# pwr.net
KiCad netlist of a schematic drawn in Altium Designer
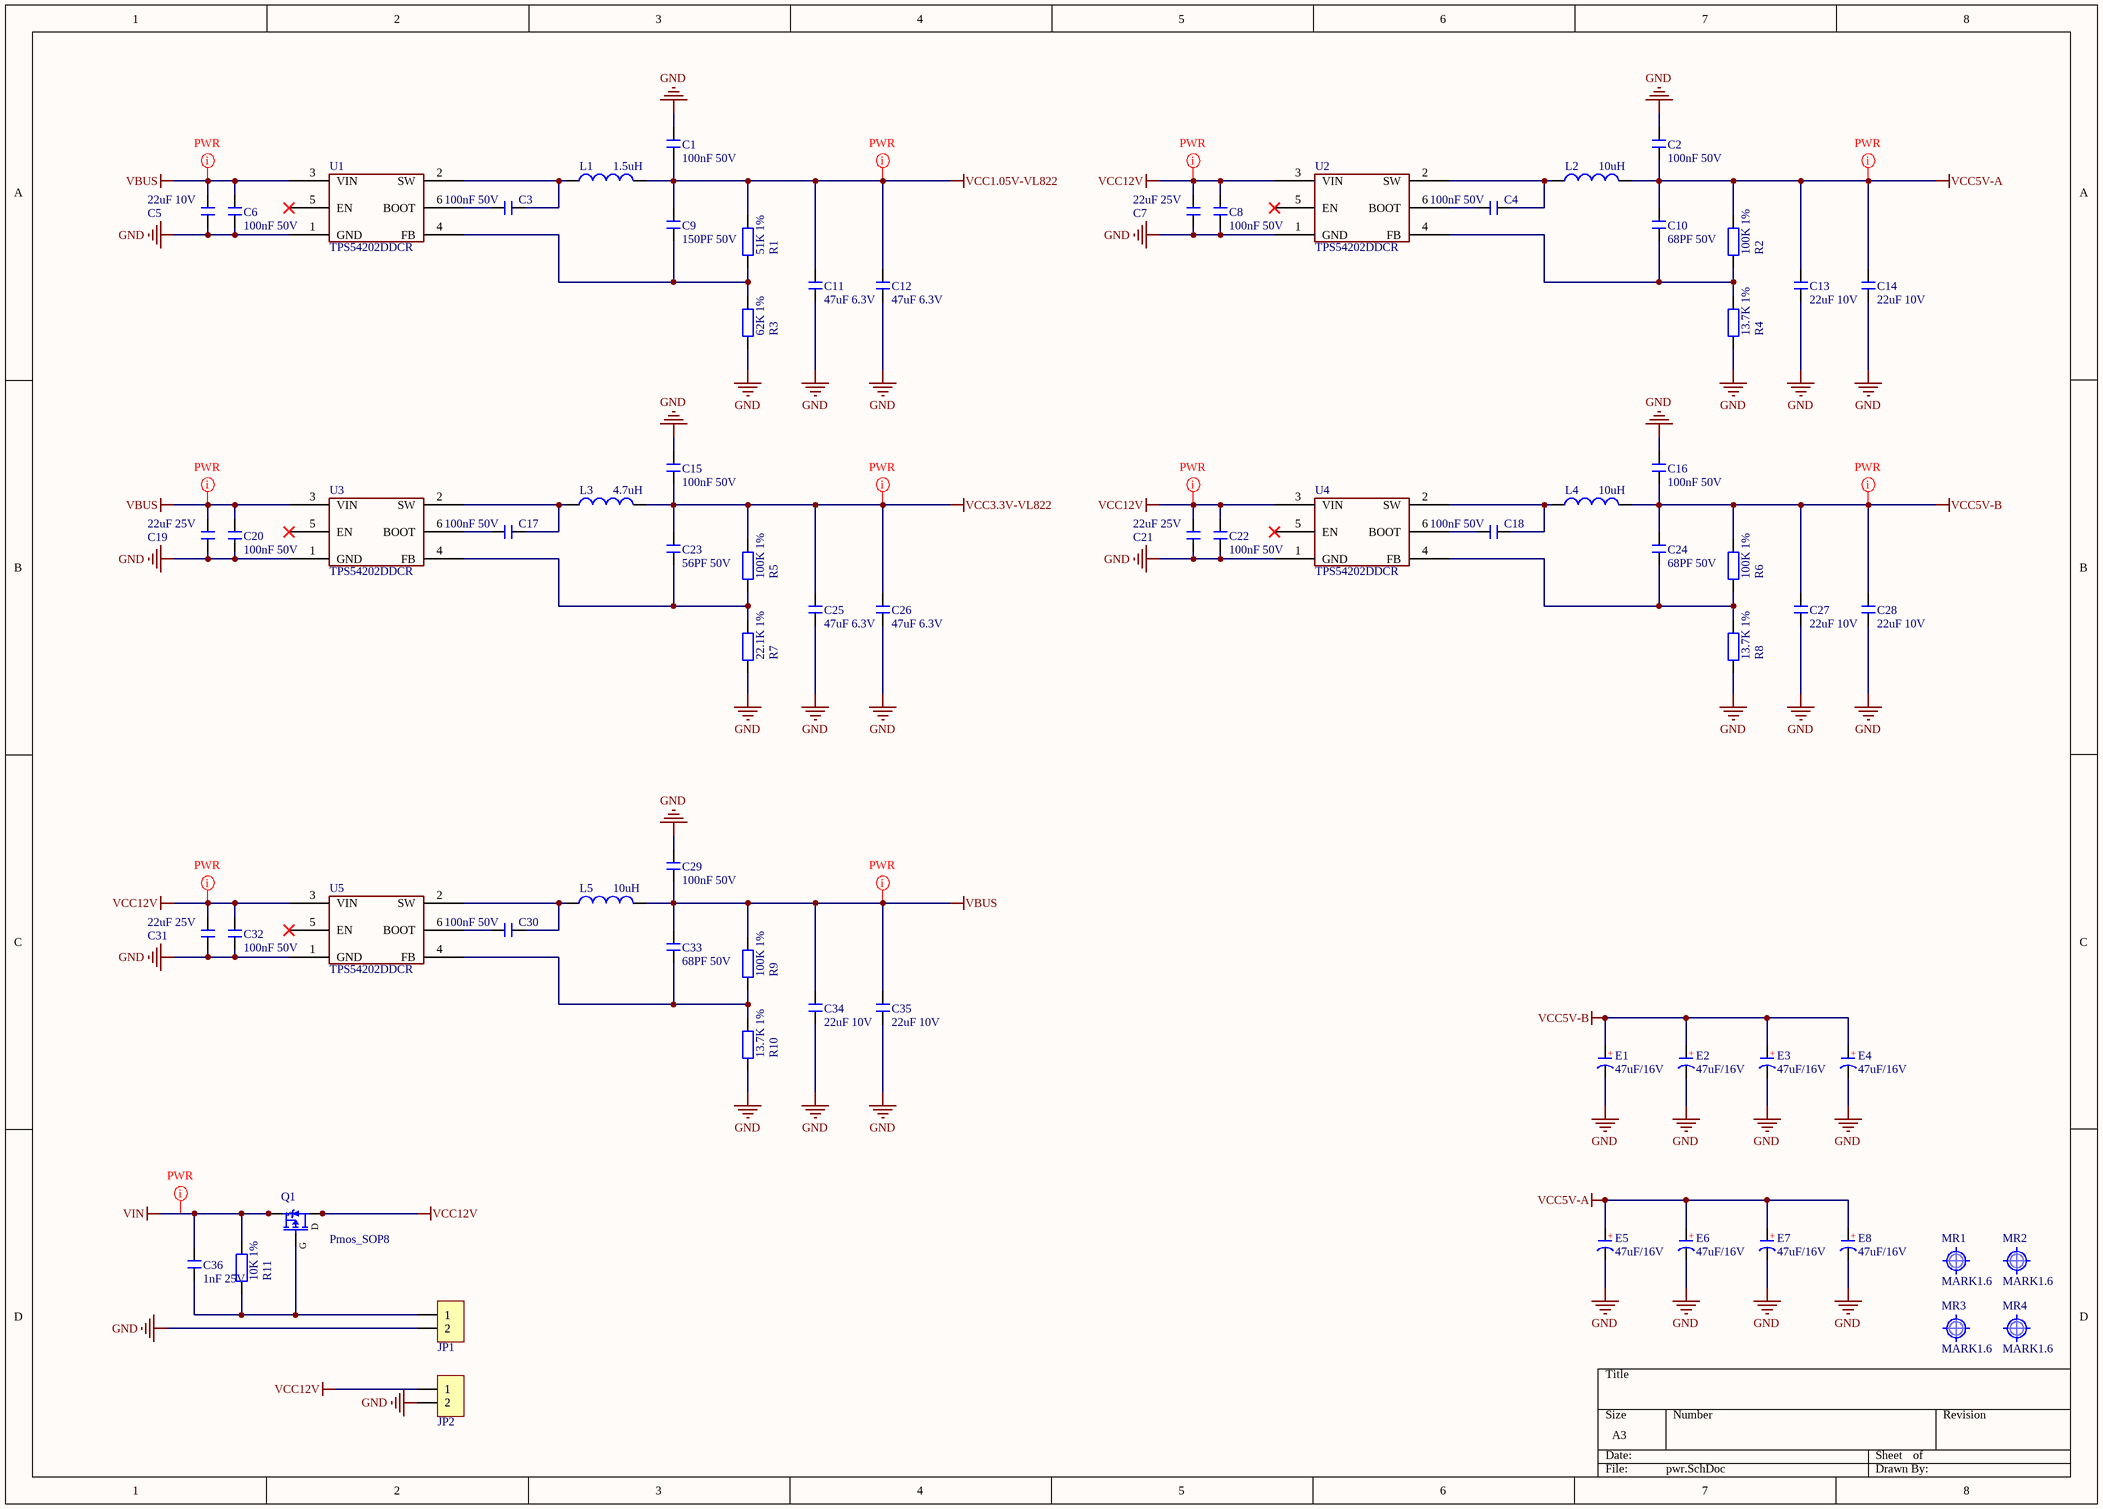
[diagram p0: pwr.SchDoc]

(export (version "E")
  (design (tool "Eeschema 10.0.6"))
  (components
    (comp (ref "C1")
      (value "100nF 50V")
      (footprint "C0402_L")
      (description "无极性贴片电容")
      (fields (field (name "版权归属") "源创客"))
      (libsource (lib "Capacitor") (part "C"))
    )
    (comp (ref "C2")
      (value "100nF 50V")
      (footprint "C0402_L")
      (description "无极性贴片电容")
      (fields (field (name "版权归属") "源创客"))
      (libsource (lib "Capacitor") (part "C"))
    )
    (comp (ref "C3")
      (value "100nF 50V")
      (footprint "C0402_L")
      (description "无极性贴片电容")
      (fields (field (name "版权归属") "源创客"))
      (libsource (lib "Capacitor") (part "C"))
    )
    (comp (ref "C4")
      (value "100nF 50V")
      (footprint "C0402_L")
      (description "无极性贴片电容")
      (fields (field (name "版权归属") "源创客"))
      (libsource (lib "Capacitor") (part "C"))
    )
    (comp (ref "C5")
      (value "22uF 10V")
      (footprint "C0805_L")
      (description "无极性贴片电容")
      (fields (field (name "版权归属") "源创客"))
      (libsource (lib "Capacitor") (part "C"))
    )
    (comp (ref "C6")
      (value "100nF 50V")
      (footprint "C0402_L")
      (description "无极性贴片电容")
      (fields (field (name "版权归属") "源创客"))
      (libsource (lib "Capacitor") (part "C"))
    )
    (comp (ref "C7")
      (value "22uF 25V")
      (footprint "C0805_L")
      (description "无极性贴片电容")
      (fields (field (name "版权归属") "源创客"))
      (libsource (lib "Capacitor") (part "C"))
    )
    (comp (ref "C8")
      (value "100nF 50V")
      (footprint "C0402_L")
      (description "无极性贴片电容")
      (fields (field (name "版权归属") "源创客"))
      (libsource (lib "Capacitor") (part "C"))
    )
    (comp (ref "C9")
      (value "150PF 50V")
      (footprint "C0402_L")
      (description "无极性贴片电容")
      (fields (field (name "版权归属") "源创客"))
      (libsource (lib "Capacitor") (part "C"))
    )
    (comp (ref "C10")
      (value "68PF 50V")
      (footprint "C0402_L")
      (description "无极性贴片电容")
      (fields (field (name "版权归属") "源创客"))
      (libsource (lib "Capacitor") (part "C"))
    )
    (comp (ref "C11")
      (value "47uF 6.3V")
      (footprint "C0805_L")
      (description "无极性贴片电容")
      (fields (field (name "版权归属") "源创客"))
      (libsource (lib "Capacitor") (part "C"))
    )
    (comp (ref "C12")
      (value "47uF 6.3V")
      (footprint "C0805_L")
      (description "无极性贴片电容")
      (fields (field (name "版权归属") "源创客"))
      (libsource (lib "Capacitor") (part "C"))
    )
    (comp (ref "C13")
      (value "22uF 10V")
      (footprint "C0805_L")
      (description "无极性贴片电容")
      (fields (field (name "版权归属") "源创客"))
      (libsource (lib "Capacitor") (part "C"))
    )
    (comp (ref "C14")
      (value "22uF 10V")
      (footprint "C0805_L")
      (description "无极性贴片电容")
      (fields (field (name "版权归属") "源创客"))
      (libsource (lib "Capacitor") (part "C"))
    )
    (comp (ref "C15")
      (value "100nF 50V")
      (footprint "C0402_L")
      (description "无极性贴片电容")
      (fields (field (name "版权归属") "源创客"))
      (libsource (lib "Capacitor") (part "C"))
    )
    (comp (ref "C16")
      (value "100nF 50V")
      (footprint "C0402_L")
      (description "无极性贴片电容")
      (fields (field (name "版权归属") "源创客"))
      (libsource (lib "Capacitor") (part "C"))
    )
    (comp (ref "C17")
      (value "100nF 50V")
      (footprint "C0402_L")
      (description "无极性贴片电容")
      (fields (field (name "版权归属") "源创客"))
      (libsource (lib "Capacitor") (part "C"))
    )
    (comp (ref "C18")
      (value "100nF 50V")
      (footprint "C0402_L")
      (description "无极性贴片电容")
      (fields (field (name "版权归属") "源创客"))
      (libsource (lib "Capacitor") (part "C"))
    )
    (comp (ref "C19")
      (value "22uF 25V")
      (footprint "C0805_L")
      (description "无极性贴片电容")
      (fields (field (name "版权归属") "源创客"))
      (libsource (lib "Capacitor") (part "C"))
    )
    (comp (ref "C20")
      (value "100nF 50V")
      (footprint "C0402_L")
      (description "无极性贴片电容")
      (fields (field (name "版权归属") "源创客"))
      (libsource (lib "Capacitor") (part "C"))
    )
    (comp (ref "C21")
      (value "22uF 25V")
      (footprint "C0805_L")
      (description "无极性贴片电容")
      (fields (field (name "版权归属") "源创客"))
      (libsource (lib "Capacitor") (part "C"))
    )
    (comp (ref "C22")
      (value "100nF 50V")
      (footprint "C0402_L")
      (description "无极性贴片电容")
      (fields (field (name "版权归属") "源创客"))
      (libsource (lib "Capacitor") (part "C"))
    )
    (comp (ref "C23")
      (value "56PF 50V")
      (footprint "C0402_L")
      (description "无极性贴片电容")
      (fields (field (name "版权归属") "源创客"))
      (libsource (lib "Capacitor") (part "C"))
    )
    (comp (ref "C24")
      (value "68PF 50V")
      (footprint "C0402_L")
      (description "无极性贴片电容")
      (fields (field (name "版权归属") "源创客"))
      (libsource (lib "Capacitor") (part "C"))
    )
    (comp (ref "C25")
      (value "47uF 6.3V")
      (footprint "C0805_L")
      (description "无极性贴片电容")
      (fields (field (name "版权归属") "源创客"))
      (libsource (lib "Capacitor") (part "C"))
    )
    (comp (ref "C26")
      (value "47uF 6.3V")
      (footprint "C0805_L")
      (description "无极性贴片电容")
      (fields (field (name "版权归属") "源创客"))
      (libsource (lib "Capacitor") (part "C"))
    )
    (comp (ref "C27")
      (value "22uF 10V")
      (footprint "C0805_L")
      (description "无极性贴片电容")
      (fields (field (name "版权归属") "源创客"))
      (libsource (lib "Capacitor") (part "C"))
    )
    (comp (ref "C28")
      (value "22uF 10V")
      (footprint "C0805_L")
      (description "无极性贴片电容")
      (fields (field (name "版权归属") "源创客"))
      (libsource (lib "Capacitor") (part "C"))
    )
    (comp (ref "C29")
      (value "100nF 50V")
      (footprint "C0402_L")
      (description "无极性贴片电容")
      (fields (field (name "版权归属") "源创客"))
      (libsource (lib "Capacitor") (part "C"))
    )
    (comp (ref "C30")
      (value "100nF 50V")
      (footprint "C0402_L")
      (description "无极性贴片电容")
      (fields (field (name "版权归属") "源创客"))
      (libsource (lib "Capacitor") (part "C"))
    )
    (comp (ref "C31")
      (value "22uF 25V")
      (footprint "C0805_L")
      (description "无极性贴片电容")
      (fields (field (name "版权归属") "源创客"))
      (libsource (lib "Capacitor") (part "C"))
    )
    (comp (ref "C32")
      (value "100nF 50V")
      (footprint "C0402_L")
      (description "无极性贴片电容")
      (fields (field (name "版权归属") "源创客"))
      (libsource (lib "Capacitor") (part "C"))
    )
    (comp (ref "C33")
      (value "68PF 50V")
      (footprint "C0402_L")
      (description "无极性贴片电容")
      (fields (field (name "版权归属") "源创客"))
      (libsource (lib "Capacitor") (part "C"))
    )
    (comp (ref "C34")
      (value "22uF 10V")
      (footprint "C0805_L")
      (description "无极性贴片电容")
      (fields (field (name "版权归属") "源创客"))
      (libsource (lib "Capacitor") (part "C"))
    )
    (comp (ref "C35")
      (value "22uF 10V")
      (footprint "C0805_L")
      (description "无极性贴片电容")
      (fields (field (name "版权归属") "源创客"))
      (libsource (lib "Capacitor") (part "C"))
    )
    (comp (ref "C36")
      (value "1nF 25V")
      (footprint "C0402_L")
      (description "无极性贴片电容")
      (fields (field (name "版权归属") "源创客"))
      (libsource (lib "Capacitor") (part "C"))
    )
    (comp (ref "E1")
      (value "47uF/16V")
      (footprint "CS 6*4 - R")
      (description "贴片电解电容")
      (fields (field (name "版权归属") "源创客"))
      (libsource (lib "Capacitor") (part "C-CD"))
    )
    (comp (ref "E2")
      (value "47uF/16V")
      (footprint "CS 6*4 - R")
      (description "贴片电解电容")
      (fields (field (name "版权归属") "源创客"))
      (libsource (lib "Capacitor") (part "C-CD"))
    )
    (comp (ref "E3")
      (value "47uF/16V")
      (footprint "CS 6*4 - R")
      (description "贴片电解电容")
      (fields (field (name "版权归属") "源创客"))
      (libsource (lib "Capacitor") (part "C-CD"))
    )
    (comp (ref "E4")
      (value "47uF/16V")
      (footprint "CS 6*4 - R")
      (description "贴片电解电容")
      (fields (field (name "版权归属") "源创客"))
      (libsource (lib "Capacitor") (part "C-CD"))
    )
    (comp (ref "E5")
      (value "47uF/16V")
      (footprint "CS 6*4 - R")
      (description "贴片电解电容")
      (fields (field (name "版权归属") "源创客"))
      (libsource (lib "Capacitor") (part "C-CD"))
    )
    (comp (ref "E6")
      (value "47uF/16V")
      (footprint "CS 6*4 - R")
      (description "贴片电解电容")
      (fields (field (name "版权归属") "源创客"))
      (libsource (lib "Capacitor") (part "C-CD"))
    )
    (comp (ref "E7")
      (value "47uF/16V")
      (footprint "CS 6*4 - R")
      (description "贴片电解电容")
      (fields (field (name "版权归属") "源创客"))
      (libsource (lib "Capacitor") (part "C-CD"))
    )
    (comp (ref "E8")
      (value "47uF/16V")
      (footprint "CS 6*4 - R")
      (description "贴片电解电容")
      (fields (field (name "版权归属") "源创客"))
      (libsource (lib "Capacitor") (part "C-CD"))
    )
    (comp (ref "JP1")
      (value "HDR-1X2")
      (footprint "ZH1.5-WS-2P")
      (description "2P接插件")
      (fields (field (name "版权归属") "源创客"))
      (libsource (lib "Connector-PinHeader") (part "Header 2"))
    )
    (comp (ref "JP2")
      (value "HDR-1X2")
      (footprint "XH2.54-WS-2P")
      (description "2P接插件")
      (fields (field (name "版权归属") "源创客"))
      (libsource (lib "Connector-PinHeader") (part "Header 2"))
    )
    (comp (ref "L1")
      (value "1.5uH")
      (footprint "SMMS0420")
      (description "小功率贴片电感")
      (fields (field (name "版权归属") "源创客"))
      (libsource (lib "Inductor") (part "L"))
    )
    (comp (ref "L2")
      (value "10uH")
      (footprint "SMMS0420")
      (description "小功率贴片电感")
      (fields (field (name "版权归属") "源创客"))
      (libsource (lib "Inductor") (part "L"))
    )
    (comp (ref "L3")
      (value "4.7uH")
      (footprint "SMMS0420")
      (description "小功率贴片电感")
      (fields (field (name "版权归属") "源创客"))
      (libsource (lib "Inductor") (part "L"))
    )
    (comp (ref "L4")
      (value "10uH")
      (footprint "SMMS0420")
      (description "小功率贴片电感")
      (fields (field (name "版权归属") "源创客"))
      (libsource (lib "Inductor") (part "L"))
    )
    (comp (ref "L5")
      (value "10uH")
      (footprint "SMMS0420")
      (description "小功率贴片电感")
      (fields (field (name "版权归属") "源创客"))
      (libsource (lib "Inductor") (part "L"))
    )
    (comp (ref "MR1")
      (value "MARK1.6")
      (footprint "Mark 1")
      (description "光学定位点")
      (fields (field (name "版权归属") "源创客"))
      (libsource (lib "Hole") (part "MARK"))
    )
    (comp (ref "MR2")
      (value "MARK1.6")
      (footprint "Mark 1")
      (description "光学定位点")
      (fields (field (name "版权归属") "源创客"))
      (libsource (lib "Hole") (part "MARK"))
    )
    (comp (ref "MR3")
      (value "MARK1.6")
      (footprint "Mark 1")
      (description "光学定位点")
      (fields (field (name "版权归属") "源创客"))
      (libsource (lib "Hole") (part "MARK"))
    )
    (comp (ref "MR4")
      (value "MARK1.6")
      (footprint "Mark 1")
      (description "光学定位点")
      (fields (field (name "版权归属") "源创客"))
      (libsource (lib "Hole") (part "MARK"))
    )
    (comp (ref "Q1")
      (value "Pmos_SOP8")
      (footprint "SOP8_L")
      (fields (field (name "版权归属") "源创客"))
      (libsource (lib "MOSFET BJT IGBT") (part "Pmos_SOP8"))
    )
    (comp (ref "R1")
      (value "51K 1%")
      (footprint "R0402_L")
      (description "贴片电阻")
      (fields (field (name "版权归属") "源创客"))
      (libsource (lib "Resistor") (part "R"))
    )
    (comp (ref "R2")
      (value "100K 1%")
      (footprint "R0402_L")
      (description "贴片电阻")
      (fields (field (name "版权归属") "源创客"))
      (libsource (lib "Resistor") (part "R"))
    )
    (comp (ref "R3")
      (value "62K 1%")
      (footprint "R0402_L")
      (description "贴片电阻")
      (fields (field (name "版权归属") "源创客"))
      (libsource (lib "Resistor") (part "R"))
    )
    (comp (ref "R4")
      (value "13.7K 1%")
      (footprint "R0402_L")
      (description "贴片电阻")
      (fields (field (name "版权归属") "源创客"))
      (libsource (lib "Resistor") (part "R"))
    )
    (comp (ref "R5")
      (value "100K 1%")
      (footprint "R0402_L")
      (description "贴片电阻")
      (fields (field (name "版权归属") "源创客"))
      (libsource (lib "Resistor") (part "R"))
    )
    (comp (ref "R6")
      (value "100K 1%")
      (footprint "R0402_L")
      (description "贴片电阻")
      (fields (field (name "版权归属") "源创客"))
      (libsource (lib "Resistor") (part "R"))
    )
    (comp (ref "R7")
      (value "22.1K 1%")
      (footprint "R0402_L")
      (description "贴片电阻")
      (fields (field (name "版权归属") "源创客"))
      (libsource (lib "Resistor") (part "R"))
    )
    (comp (ref "R8")
      (value "13.7K 1%")
      (footprint "R0402_L")
      (description "贴片电阻")
      (fields (field (name "版权归属") "源创客"))
      (libsource (lib "Resistor") (part "R"))
    )
    (comp (ref "R9")
      (value "100K 1%")
      (footprint "R0402_L")
      (description "贴片电阻")
      (fields (field (name "版权归属") "源创客"))
      (libsource (lib "Resistor") (part "R"))
    )
    (comp (ref "R10")
      (value "13.7K 1%")
      (footprint "R0402_L")
      (description "贴片电阻")
      (fields (field (name "版权归属") "源创客"))
      (libsource (lib "Resistor") (part "R"))
    )
    (comp (ref "R11")
      (value "10K 1%")
      (footprint "R0402_L")
      (description "贴片电阻")
      (fields (field (name "版权归属") "源创客"))
      (libsource (lib "Resistor") (part "R"))
    )
    (comp (ref "U1")
      (value "TPS54202DDCR")
      (footprint "SOT23-6L")
      (description "DCDC Convert")
      (libsource (lib "DCDC Convert") (part "TPS54202DDCR"))
    )
    (comp (ref "U2")
      (value "TPS54202DDCR")
      (footprint "SOT23-6L")
      (description "DCDC Convert")
      (libsource (lib "DCDC Convert") (part "TPS54202DDCR"))
    )
    (comp (ref "U3")
      (value "TPS54202DDCR")
      (footprint "SOT23-6L")
      (description "DCDC Convert")
      (libsource (lib "DCDC Convert") (part "TPS54202DDCR"))
    )
    (comp (ref "U4")
      (value "TPS54202DDCR")
      (footprint "SOT23-6L")
      (description "DCDC Convert")
      (libsource (lib "DCDC Convert") (part "TPS54202DDCR"))
    )
    (comp (ref "U5")
      (value "TPS54202DDCR")
      (footprint "SOT23-6L")
      (description "DCDC Convert")
      (libsource (lib "DCDC Convert") (part "TPS54202DDCR"))
    )
  )
  (nets
    (net (code "1") (name "GND") (class "Default")
      (node (ref "C1") (pin "2") (pinfunction "2_2") (pintype "passive"))
      (node (ref "C11") (pin "2") (pinfunction "2_2") (pintype "passive"))
      (node (ref "C12") (pin "2") (pinfunction "2_2") (pintype "passive"))
      (node (ref "C13") (pin "2") (pinfunction "2_2") (pintype "passive"))
      (node (ref "C14") (pin "2") (pinfunction "2_2") (pintype "passive"))
      (node (ref "C15") (pin "2") (pinfunction "2_2") (pintype "passive"))
      (node (ref "C16") (pin "2") (pinfunction "2_2") (pintype "passive"))
      (node (ref "C19") (pin "1") (pinfunction "1_1") (pintype "passive"))
      (node (ref "C2") (pin "2") (pinfunction "2_2") (pintype "passive"))
      (node (ref "C20") (pin "1") (pinfunction "1_1") (pintype "passive"))
      (node (ref "C21") (pin "1") (pinfunction "1_1") (pintype "passive"))
      (node (ref "C22") (pin "1") (pinfunction "1_1") (pintype "passive"))
      (node (ref "C25") (pin "2") (pinfunction "2_2") (pintype "passive"))
      (node (ref "C26") (pin "2") (pinfunction "2_2") (pintype "passive"))
      (node (ref "C27") (pin "2") (pinfunction "2_2") (pintype "passive"))
      (node (ref "C28") (pin "2") (pinfunction "2_2") (pintype "passive"))
      (node (ref "C29") (pin "2") (pinfunction "2_2") (pintype "passive"))
      (node (ref "C31") (pin "1") (pinfunction "1_1") (pintype "passive"))
      (node (ref "C32") (pin "1") (pinfunction "1_1") (pintype "passive"))
      (node (ref "C34") (pin "2") (pinfunction "2_2") (pintype "passive"))
      (node (ref "C35") (pin "2") (pinfunction "2_2") (pintype "passive"))
      (node (ref "C5") (pin "1") (pinfunction "1_1") (pintype "passive"))
      (node (ref "C6") (pin "1") (pinfunction "1_1") (pintype "passive"))
      (node (ref "C7") (pin "1") (pinfunction "1_1") (pintype "passive"))
      (node (ref "C8") (pin "1") (pinfunction "1_1") (pintype "passive"))
      (node (ref "E1") (pin "2") (pinfunction "K_2") (pintype "passive"))
      (node (ref "E2") (pin "2") (pinfunction "K_2") (pintype "passive"))
      (node (ref "E3") (pin "2") (pinfunction "K_2") (pintype "passive"))
      (node (ref "E4") (pin "2") (pinfunction "K_2") (pintype "passive"))
      (node (ref "E5") (pin "2") (pinfunction "K_2") (pintype "passive"))
      (node (ref "E6") (pin "2") (pinfunction "K_2") (pintype "passive"))
      (node (ref "E7") (pin "2") (pinfunction "K_2") (pintype "passive"))
      (node (ref "E8") (pin "2") (pinfunction "K_2") (pintype "passive"))
      (node (ref "JP1") (pin "2") (pinfunction "2_2") (pintype "passive"))
      (node (ref "JP2") (pin "2") (pinfunction "2_2") (pintype "passive"))
      (node (ref "R10") (pin "2") (pinfunction "2_2") (pintype "passive"))
      (node (ref "R3") (pin "2") (pinfunction "2_2") (pintype "passive"))
      (node (ref "R4") (pin "2") (pinfunction "2_2") (pintype "passive"))
      (node (ref "R7") (pin "2") (pinfunction "2_2") (pintype "passive"))
      (node (ref "R8") (pin "2") (pinfunction "2_2") (pintype "passive"))
      (node (ref "U1") (pin "1") (pinfunction "GND_1") (pintype "passive"))
      (node (ref "U2") (pin "1") (pinfunction "GND_1") (pintype "passive"))
      (node (ref "U3") (pin "1") (pinfunction "GND_1") (pintype "passive"))
      (node (ref "U4") (pin "1") (pinfunction "GND_1") (pintype "passive"))
      (node (ref "U5") (pin "1") (pinfunction "GND_1") (pintype "passive"))
    )
    (net (code "2") (name "Net-(Q1-G)") (class "Default")
      (node (ref "C36") (pin "2") (pinfunction "2_2") (pintype "passive"))
      (node (ref "JP1") (pin "1") (pinfunction "1_1") (pintype "passive"))
      (node (ref "Q1") (pin "4") (pinfunction "G_4") (pintype "passive"))
      (node (ref "R11") (pin "2") (pinfunction "2_2") (pintype "passive"))
    )
    (net (code "3") (name "Net-(U1-BOOT)") (class "Default")
      (node (ref "C3") (pin "1") (pinfunction "1_1") (pintype "passive"))
      (node (ref "U1") (pin "6") (pinfunction "BOOT_6") (pintype "passive"))
    )
    (net (code "4") (name "Net-(U1-FB)") (class "Default")
      (node (ref "C9") (pin "1") (pinfunction "1_1") (pintype "passive"))
      (node (ref "R1") (pin "2") (pinfunction "2_2") (pintype "passive"))
      (node (ref "R3") (pin "1") (pinfunction "1_1") (pintype "passive"))
      (node (ref "U1") (pin "4") (pinfunction "FB_4") (pintype "passive"))
    )
    (net (code "5") (name "Net-(U1-SW)") (class "Default")
      (node (ref "C3") (pin "2") (pinfunction "2_2") (pintype "passive"))
      (node (ref "L1") (pin "1") (pinfunction "1_1") (pintype "passive"))
      (node (ref "U1") (pin "2") (pinfunction "SW_2") (pintype "passive"))
    )
    (net (code "6") (name "Net-(U2-BOOT)") (class "Default")
      (node (ref "C4") (pin "1") (pinfunction "1_1") (pintype "passive"))
      (node (ref "U2") (pin "6") (pinfunction "BOOT_6") (pintype "passive"))
    )
    (net (code "7") (name "Net-(U2-FB)") (class "Default")
      (node (ref "C10") (pin "1") (pinfunction "1_1") (pintype "passive"))
      (node (ref "R2") (pin "2") (pinfunction "2_2") (pintype "passive"))
      (node (ref "R4") (pin "1") (pinfunction "1_1") (pintype "passive"))
      (node (ref "U2") (pin "4") (pinfunction "FB_4") (pintype "passive"))
    )
    (net (code "8") (name "Net-(U2-SW)") (class "Default")
      (node (ref "C4") (pin "2") (pinfunction "2_2") (pintype "passive"))
      (node (ref "L2") (pin "1") (pinfunction "1_1") (pintype "passive"))
      (node (ref "U2") (pin "2") (pinfunction "SW_2") (pintype "passive"))
    )
    (net (code "9") (name "Net-(U3-BOOT)") (class "Default")
      (node (ref "C17") (pin "1") (pinfunction "1_1") (pintype "passive"))
      (node (ref "U3") (pin "6") (pinfunction "BOOT_6") (pintype "passive"))
    )
    (net (code "10") (name "Net-(U3-FB)") (class "Default")
      (node (ref "C23") (pin "1") (pinfunction "1_1") (pintype "passive"))
      (node (ref "R5") (pin "2") (pinfunction "2_2") (pintype "passive"))
      (node (ref "R7") (pin "1") (pinfunction "1_1") (pintype "passive"))
      (node (ref "U3") (pin "4") (pinfunction "FB_4") (pintype "passive"))
    )
    (net (code "11") (name "Net-(U3-SW)") (class "Default")
      (node (ref "C17") (pin "2") (pinfunction "2_2") (pintype "passive"))
      (node (ref "L3") (pin "1") (pinfunction "1_1") (pintype "passive"))
      (node (ref "U3") (pin "2") (pinfunction "SW_2") (pintype "passive"))
    )
    (net (code "12") (name "Net-(U4-BOOT)") (class "Default")
      (node (ref "C18") (pin "1") (pinfunction "1_1") (pintype "passive"))
      (node (ref "U4") (pin "6") (pinfunction "BOOT_6") (pintype "passive"))
    )
    (net (code "13") (name "Net-(U4-FB)") (class "Default")
      (node (ref "C24") (pin "1") (pinfunction "1_1") (pintype "passive"))
      (node (ref "R6") (pin "2") (pinfunction "2_2") (pintype "passive"))
      (node (ref "R8") (pin "1") (pinfunction "1_1") (pintype "passive"))
      (node (ref "U4") (pin "4") (pinfunction "FB_4") (pintype "passive"))
    )
    (net (code "14") (name "Net-(U4-SW)") (class "Default")
      (node (ref "C18") (pin "2") (pinfunction "2_2") (pintype "passive"))
      (node (ref "L4") (pin "1") (pinfunction "1_1") (pintype "passive"))
      (node (ref "U4") (pin "2") (pinfunction "SW_2") (pintype "passive"))
    )
    (net (code "15") (name "Net-(U5-BOOT)") (class "Default")
      (node (ref "C30") (pin "1") (pinfunction "1_1") (pintype "passive"))
      (node (ref "U5") (pin "6") (pinfunction "BOOT_6") (pintype "passive"))
    )
    (net (code "16") (name "Net-(U5-FB)") (class "Default")
      (node (ref "C33") (pin "1") (pinfunction "1_1") (pintype "passive"))
      (node (ref "R10") (pin "1") (pinfunction "1_1") (pintype "passive"))
      (node (ref "R9") (pin "2") (pinfunction "2_2") (pintype "passive"))
      (node (ref "U5") (pin "4") (pinfunction "FB_4") (pintype "passive"))
    )
    (net (code "17") (name "Net-(U5-SW)") (class "Default")
      (node (ref "C30") (pin "2") (pinfunction "2_2") (pintype "passive"))
      (node (ref "L5") (pin "1") (pinfunction "1_1") (pintype "passive"))
      (node (ref "U5") (pin "2") (pinfunction "SW_2") (pintype "passive"))
    )
    (net (code "18") (name "VBUS") (class "Default")
      (node (ref "C19") (pin "2") (pinfunction "2_2") (pintype "passive"))
      (node (ref "C20") (pin "2") (pinfunction "2_2") (pintype "passive"))
      (node (ref "C29") (pin "1") (pinfunction "1_1") (pintype "passive"))
      (node (ref "C33") (pin "2") (pinfunction "2_2") (pintype "passive"))
      (node (ref "C34") (pin "1") (pinfunction "1_1") (pintype "passive"))
      (node (ref "C35") (pin "1") (pinfunction "1_1") (pintype "passive"))
      (node (ref "C5") (pin "2") (pinfunction "2_2") (pintype "passive"))
      (node (ref "C6") (pin "2") (pinfunction "2_2") (pintype "passive"))
      (node (ref "L5") (pin "2") (pinfunction "2_2") (pintype "passive"))
      (node (ref "R9") (pin "1") (pinfunction "1_1") (pintype "passive"))
      (node (ref "U1") (pin "3") (pinfunction "VIN_3") (pintype "passive"))
      (node (ref "U3") (pin "3") (pinfunction "VIN_3") (pintype "passive"))
    )
    (net (code "19") (name "VCC1.05V-VL822") (class "Default")
      (node (ref "C1") (pin "1") (pinfunction "1_1") (pintype "passive"))
      (node (ref "C11") (pin "1") (pinfunction "1_1") (pintype "passive"))
      (node (ref "C12") (pin "1") (pinfunction "1_1") (pintype "passive"))
      (node (ref "C9") (pin "2") (pinfunction "2_2") (pintype "passive"))
      (node (ref "L1") (pin "2") (pinfunction "2_2") (pintype "passive"))
      (node (ref "R1") (pin "1") (pinfunction "1_1") (pintype "passive"))
    )
    (net (code "20") (name "VCC3.3V-VL822") (class "Default")
      (node (ref "C15") (pin "1") (pinfunction "1_1") (pintype "passive"))
      (node (ref "C23") (pin "2") (pinfunction "2_2") (pintype "passive"))
      (node (ref "C25") (pin "1") (pinfunction "1_1") (pintype "passive"))
      (node (ref "C26") (pin "1") (pinfunction "1_1") (pintype "passive"))
      (node (ref "L3") (pin "2") (pinfunction "2_2") (pintype "passive"))
      (node (ref "R5") (pin "1") (pinfunction "1_1") (pintype "passive"))
    )
    (net (code "21") (name "VCC5V-A") (class "Default")
      (node (ref "C10") (pin "2") (pinfunction "2_2") (pintype "passive"))
      (node (ref "C13") (pin "1") (pinfunction "1_1") (pintype "passive"))
      (node (ref "C14") (pin "1") (pinfunction "1_1") (pintype "passive"))
      (node (ref "C2") (pin "1") (pinfunction "1_1") (pintype "passive"))
      (node (ref "E5") (pin "1") (pinfunction "A_1") (pintype "passive"))
      (node (ref "E6") (pin "1") (pinfunction "A_1") (pintype "passive"))
      (node (ref "E7") (pin "1") (pinfunction "A_1") (pintype "passive"))
      (node (ref "E8") (pin "1") (pinfunction "A_1") (pintype "passive"))
      (node (ref "L2") (pin "2") (pinfunction "2_2") (pintype "passive"))
      (node (ref "R2") (pin "1") (pinfunction "1_1") (pintype "passive"))
    )
    (net (code "22") (name "VCC5V-B") (class "Default")
      (node (ref "C16") (pin "1") (pinfunction "1_1") (pintype "passive"))
      (node (ref "C24") (pin "2") (pinfunction "2_2") (pintype "passive"))
      (node (ref "C27") (pin "1") (pinfunction "1_1") (pintype "passive"))
      (node (ref "C28") (pin "1") (pinfunction "1_1") (pintype "passive"))
      (node (ref "E1") (pin "1") (pinfunction "A_1") (pintype "passive"))
      (node (ref "E2") (pin "1") (pinfunction "A_1") (pintype "passive"))
      (node (ref "E3") (pin "1") (pinfunction "A_1") (pintype "passive"))
      (node (ref "E4") (pin "1") (pinfunction "A_1") (pintype "passive"))
      (node (ref "L4") (pin "2") (pinfunction "2_2") (pintype "passive"))
      (node (ref "R6") (pin "1") (pinfunction "1_1") (pintype "passive"))
    )
    (net (code "23") (name "VCC12V") (class "Default")
      (node (ref "C21") (pin "2") (pinfunction "2_2") (pintype "passive"))
      (node (ref "C22") (pin "2") (pinfunction "2_2") (pintype "passive"))
      (node (ref "C31") (pin "2") (pinfunction "2_2") (pintype "passive"))
      (node (ref "C32") (pin "2") (pinfunction "2_2") (pintype "passive"))
      (node (ref "C7") (pin "2") (pinfunction "2_2") (pintype "passive"))
      (node (ref "C8") (pin "2") (pinfunction "2_2") (pintype "passive"))
      (node (ref "JP2") (pin "1") (pinfunction "1_1") (pintype "passive"))
      (node (ref "Q1") (pin "5") (pinfunction "D_5") (pintype "passive"))
      (node (ref "Q1") (pin "6") (pinfunction "D_6") (pintype "passive"))
      (node (ref "Q1") (pin "7") (pinfunction "D_7") (pintype "passive"))
      (node (ref "Q1") (pin "8") (pinfunction "D_8") (pintype "passive"))
      (node (ref "U2") (pin "3") (pinfunction "VIN_3") (pintype "passive"))
      (node (ref "U4") (pin "3") (pinfunction "VIN_3") (pintype "passive"))
      (node (ref "U5") (pin "3") (pinfunction "VIN_3") (pintype "passive"))
    )
    (net (code "24") (name "VIN") (class "Default")
      (node (ref "C36") (pin "1") (pinfunction "1_1") (pintype "passive"))
      (node (ref "Q1") (pin "1") (pinfunction "S_1") (pintype "passive"))
      (node (ref "Q1") (pin "2") (pinfunction "S_2") (pintype "passive"))
      (node (ref "Q1") (pin "3") (pinfunction "S_3") (pintype "passive"))
      (node (ref "R11") (pin "1") (pinfunction "1_1") (pintype "passive"))
    )
    (net (code "25") (name "unconnected-(U1-EN-Pad5)") (class "Default")
      (node (ref "U1") (pin "5") (pinfunction "EN_5") (pintype "passive+no_connect"))
    )
    (net (code "26") (name "unconnected-(U2-EN-Pad5)") (class "Default")
      (node (ref "U2") (pin "5") (pinfunction "EN_5") (pintype "passive+no_connect"))
    )
    (net (code "27") (name "unconnected-(U3-EN-Pad5)") (class "Default")
      (node (ref "U3") (pin "5") (pinfunction "EN_5") (pintype "passive+no_connect"))
    )
    (net (code "28") (name "unconnected-(U4-EN-Pad5)") (class "Default")
      (node (ref "U4") (pin "5") (pinfunction "EN_5") (pintype "passive+no_connect"))
    )
    (net (code "29") (name "unconnected-(U5-EN-Pad5)") (class "Default")
      (node (ref "U5") (pin "5") (pinfunction "EN_5") (pintype "passive+no_connect"))
    )
  )
)
